# esp32.net
KiCad netlist of a schematic drawn in Altium Designer
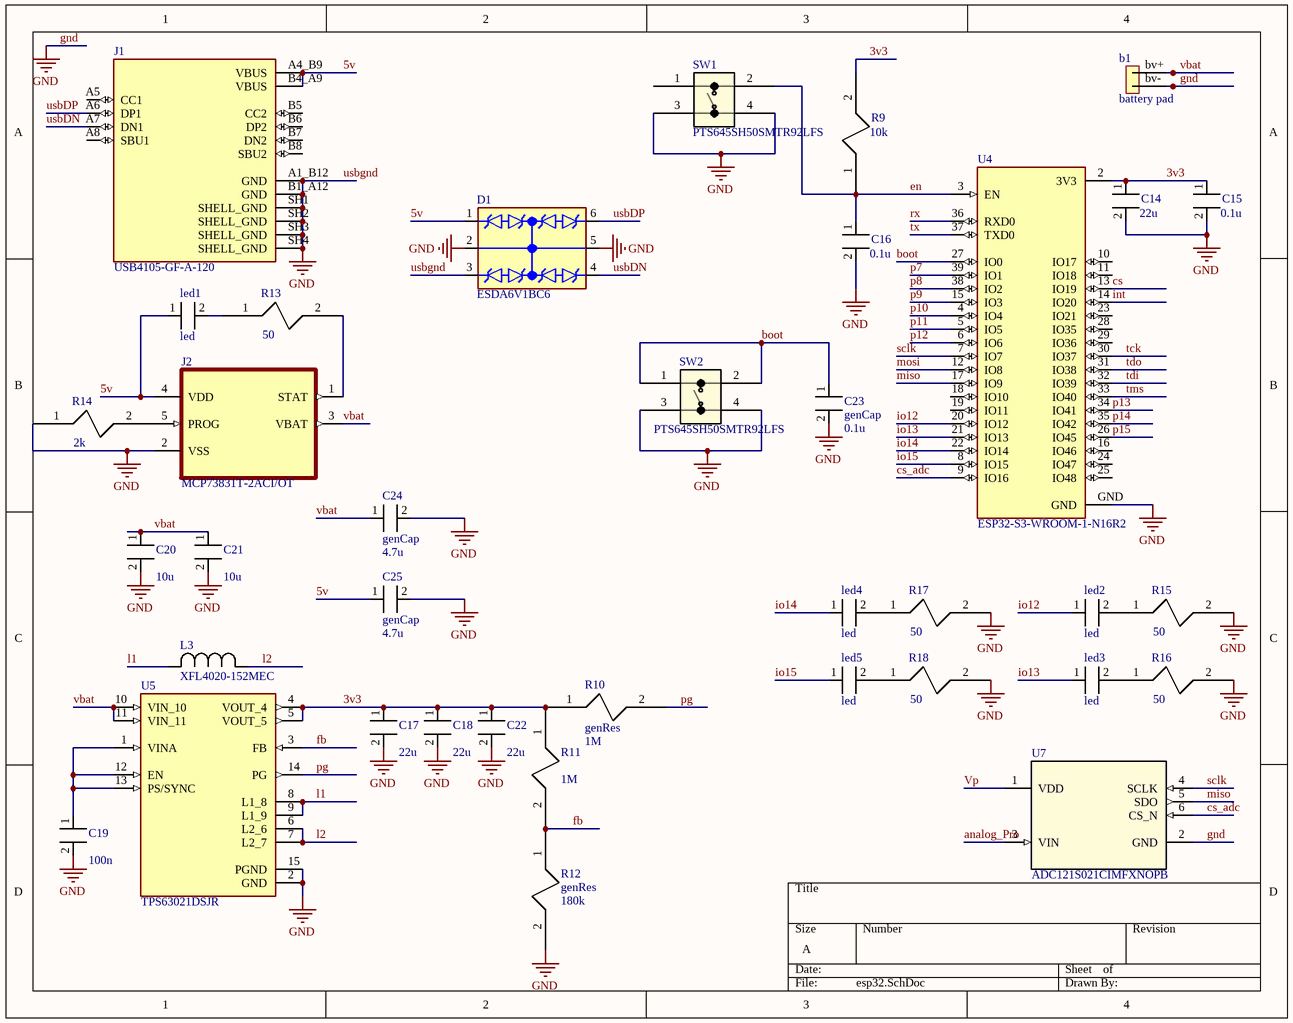
[diagram p0: esp32.SchDoc]

(export (version "E")
  (design (tool "Eeschema 10.0.6"))
  (components
    (comp (ref "b1")
      (value "battery pad")
      (footprint "bat_pads")
      (libsource (lib "sEMG_lib") (part "battery pad"))
    )
    (comp (ref "C14")
      (value "genCap")
      (footprint "GeneralCap")
      (description "C86295")
      (fields (field (name "C") "22u"))
      (libsource (lib "seniorDesign") (part "genCap"))
    )
    (comp (ref "C15")
      (value "genCap")
      (footprint "GeneralCap")
      (description "C14663")
      (fields (field (name "C") "0.1u"))
      (libsource (lib "seniorDesign") (part "genCap"))
    )
    (comp (ref "C16")
      (value "genCap")
      (footprint "GeneralCap")
      (description "C14663")
      (fields (field (name "C") "0.1u"))
      (libsource (lib "seniorDesign") (part "genCap"))
    )
    (comp (ref "C17")
      (value "genCap")
      (footprint "GeneralCap")
      (description "C86295")
      (fields (field (name "C") "22u"))
      (libsource (lib "seniorDesign") (part "genCap"))
    )
    (comp (ref "C18")
      (value "genCap")
      (footprint "GeneralCap")
      (description "C86295")
      (fields (field (name "C") "22u"))
      (libsource (lib "seniorDesign") (part "genCap"))
    )
    (comp (ref "C19")
      (value "genCap")
      (footprint "GeneralCap")
      (description "C14663")
      (fields (field (name "C") "100n"))
      (libsource (lib "seniorDesign") (part "genCap"))
    )
    (comp (ref "C20")
      (value "genCap")
      (footprint "GeneralCap")
      (description "C6119842")
      (fields (field (name "C") "10u"))
      (libsource (lib "seniorDesign") (part "genCap"))
    )
    (comp (ref "C21")
      (value "genCap")
      (footprint "GeneralCap")
      (description "C6119842")
      (fields (field (name "C") "10u"))
      (libsource (lib "seniorDesign") (part "genCap"))
    )
    (comp (ref "C22")
      (value "genCap")
      (footprint "GeneralCap")
      (description "C86295")
      (fields (field (name "C") "22u"))
      (libsource (lib "seniorDesign") (part "genCap"))
    )
    (comp (ref "C23")
      (value "genCap")
      (footprint "GeneralCap")
      (description "C14663")
      (fields (field (name "C") "0.1u"))
      (libsource (lib "seniorDesign") (part "genCap"))
    )
    (comp (ref "C24")
      (value "genCap")
      (footprint "GeneralCap")
      (description "C19666")
      (fields (field (name "C") "4.7u"))
      (libsource (lib "seniorDesign") (part "genCap"))
    )
    (comp (ref "C25")
      (value "genCap")
      (footprint "GeneralCap")
      (description "C19666")
      (fields (field (name "C") "4.7u"))
      (libsource (lib "seniorDesign") (part "genCap"))
    )
    (comp (ref "D1")
      (value "ESDA6V1BC6")
      (footprint "SOT95P280X145-6N")
      (description "C495220")
      (fields (field (name "MF") "STMicroelectronics"))
      (libsource (lib "ESDA6V1BC6") (part "ESDA6V1BC6"))
    )
    (comp (ref "J1")
      (value "USB4105-GF-A-120")
      (footprint "GCT_USB4105-GF-A-120")
      (fields (field (name "MF") "Global Connector Technology") (field (name "MP") "USB4105GFA120"))
      (libsource (lib "USB4105-GF-A-120") (part "USB4105-GF-A-120"))
    )
    (comp (ref "J2")
      (value "MCP73831T-2ACI/OT")
      (footprint "SOT95P280X145-5N")
      (description "C424093")
      (fields (field (name "MF") "Microchip"))
      (libsource (lib "MCP73831T-2ACI_OT") (part "MCP73831T-2ACI/OT"))
    )
    (comp (ref "L3")
      (value "XFL4020-152MEC")
      (footprint "IND_XFL4020_COC")
      (description "C3033018")
      (libsource (lib "XFL4020-152MEC") (part "XFL4020-152MEC"))
    )
    (comp (ref "led1")
      (value "led")
      (footprint "GeneralCap")
      (description "C965799")
      (libsource (lib "seniorDesign") (part "genCap"))
    )
    (comp (ref "led2")
      (value "led")
      (footprint "GeneralCap")
      (description "C965799")
      (libsource (lib "seniorDesign") (part "genCap"))
    )
    (comp (ref "led3")
      (value "led")
      (footprint "GeneralCap")
      (description "C965799")
      (libsource (lib "seniorDesign") (part "genCap"))
    )
    (comp (ref "led4")
      (value "led")
      (footprint "GeneralCap")
      (description "C965799")
      (libsource (lib "seniorDesign") (part "genCap"))
    )
    (comp (ref "led5")
      (value "led")
      (footprint "GeneralCap")
      (description "C965799")
      (libsource (lib "seniorDesign") (part "genCap"))
    )
    (comp (ref "R9")
      (value "genRes")
      (footprint "GeneralCap")
      (description "C98220")
      (fields (field (name "R") "10k"))
      (libsource (lib "seniorDesign") (part "genRes"))
    )
    (comp (ref "R10")
      (value "genRes")
      (footprint "GeneralCap")
      (description "C105578")
      (fields (field (name "R") "1M"))
      (libsource (lib "seniorDesign") (part "genRes"))
    )
    (comp (ref "R11")
      (value "genRes")
      (footprint "GeneralCap")
      (description "C105578")
      (fields (field (name "R") "1M"))
      (libsource (lib "seniorDesign") (part "genRes"))
    )
    (comp (ref "R12")
      (value "genRes")
      (footprint "GeneralCap")
      (description "C123419")
      (fields (field (name "R") "180k"))
      (libsource (lib "seniorDesign") (part "genRes"))
    )
    (comp (ref "R13")
      (value "genRes")
      (footprint "GeneralCap")
      (description "C844932")
      (fields (field (name "R") "50"))
      (libsource (lib "seniorDesign") (part "genRes"))
    )
    (comp (ref "R14")
      (value "genRes")
      (footprint "GeneralCap")
      (description "C22975")
      (fields (field (name "R") "2k"))
      (libsource (lib "seniorDesign") (part "genRes"))
    )
    (comp (ref "R15")
      (value "genRes")
      (footprint "GeneralCap")
      (description "C844932")
      (fields (field (name "R") "50"))
      (libsource (lib "seniorDesign") (part "genRes"))
    )
    (comp (ref "R16")
      (value "genRes")
      (footprint "GeneralCap")
      (description "C844932")
      (fields (field (name "R") "50"))
      (libsource (lib "seniorDesign") (part "genRes"))
    )
    (comp (ref "R17")
      (value "genRes")
      (footprint "GeneralCap")
      (description "C844932")
      (fields (field (name "R") "50"))
      (libsource (lib "seniorDesign") (part "genRes"))
    )
    (comp (ref "R18")
      (value "genRes")
      (footprint "GeneralCap")
      (description "C844932")
      (fields (field (name "R") "50"))
      (libsource (lib "seniorDesign") (part "genRes"))
    )
    (comp (ref "SW1")
      (value "PTS645SH50SMTR92LFS")
      (footprint "PTS645S_SMTR92_CNK")
      (description "C221869")
      (libsource (lib "PTS645SH50SMTR92LFS") (part "PTS645SH50SMTR92LFS"))
    )
    (comp (ref "SW2")
      (value "PTS645SH50SMTR92LFS")
      (footprint "PTS645S_SMTR92_CNK")
      (description "C221869")
      (libsource (lib "PTS645SH50SMTR92LFS") (part "PTS645SH50SMTR92LFS"))
    )
    (comp (ref "U4")
      (value "ESP32-S3-WROOM-1-N16R2")
      (footprint "XCVR_ESP32-S3-WROOM-1-N16R2")
      (description "C2913205")
      (fields (field (name "MF") "Espressif Systems") (field (name "MP") "ESP32S3WROOM1N16R2"))
      (libsource (lib "ESP32-S3-WROOM-1-N16R2") (part "ESP32-S3-WROOM-1-N16R2"))
    )
    (comp (ref "U5")
      (value "TPS63021DSJR")
      (footprint "IC_TPS63021DSJR")
      (libsource (lib "TPS63021DSJR") (part "TPS63021DSJR"))
    )
    (comp (ref "U7")
      (value "ADC121S021CIMFXNOPB")
      (footprint "DBV0006A_N")
      (description "C701596")
      (libsource (lib "ADC121S021CIMFXNOPB") (part "ADC121S021CIMFXNOPB"))
    )
  )
  (nets
    (net (code "1") (name "/3v3") (class "Default")
      (node (ref "C14") (pin "1") (pinfunction "1_1") (pintype "passive"))
      (node (ref "C15") (pin "1") (pinfunction "1_1") (pintype "passive"))
      (node (ref "C17") (pin "1") (pinfunction "1_1") (pintype "passive"))
      (node (ref "C18") (pin "1") (pinfunction "1_1") (pintype "passive"))
      (node (ref "C22") (pin "1") (pinfunction "1_1") (pintype "passive"))
      (node (ref "R10") (pin "1") (pinfunction "1_1") (pintype "passive"))
      (node (ref "R11") (pin "1") (pinfunction "1_1") (pintype "passive"))
      (node (ref "R9") (pin "2") (pinfunction "2_2") (pintype "passive"))
      (node (ref "U4") (pin "2") (pinfunction "3V3_2") (pintype "power_in"))
      (node (ref "U5") (pin "4") (pinfunction "VOUT_4_4") (pintype "output"))
      (node (ref "U5") (pin "5") (pinfunction "VOUT_5_5") (pintype "output"))
    )
    (net (code "2") (name "/5v") (class "Default")
      (node (ref "C25") (pin "1") (pinfunction "1_1") (pintype "passive"))
      (node (ref "D1") (pin "1") (pinfunction "C1_1") (pintype "passive"))
      (node (ref "J1") (pin "A4_B9") (pinfunction "VBUS_A4_B9") (pintype "power_in"))
      (node (ref "J1") (pin "B4_A9") (pinfunction "VBUS_B4_A9") (pintype "power_in"))
      (node (ref "J2") (pin "4") (pinfunction "VDD_4") (pintype "power_in"))
      (node (ref "led1") (pin "1") (pinfunction "1_1") (pintype "passive"))
    )
    (net (code "3") (name "/Vp") (class "Default")
      (node (ref "U7") (pin "1") (pinfunction "VDD_1") (pintype "power_in"))
    )
    (net (code "4") (name "/analog_Pro") (class "Default")
      (node (ref "U7") (pin "3") (pinfunction "VIN_3") (pintype "input"))
    )
    (net (code "5") (name "/boot") (class "Default")
      (node (ref "C23") (pin "1") (pinfunction "1_1") (pintype "passive"))
      (node (ref "SW2") (pin "1") (pinfunction "1_1") (pintype "passive"))
      (node (ref "SW2") (pin "2") (pinfunction "2_2") (pintype "passive"))
      (node (ref "U4") (pin "27") (pinfunction "IO0_27") (pintype "bidirectional"))
    )
    (net (code "6") (name "/cs") (class "Default")
      (node (ref "U4") (pin "13") (pinfunction "IO19_13") (pintype "bidirectional"))
    )
    (net (code "7") (name "/cs_adc") (class "Default")
      (node (ref "U4") (pin "9") (pinfunction "IO16_9") (pintype "bidirectional"))
      (node (ref "U7") (pin "6") (pinfunction "CS_N_6") (pintype "input"))
    )
    (net (code "8") (name "/en") (class "Default")
      (node (ref "C16") (pin "1") (pinfunction "1_1") (pintype "passive"))
      (node (ref "R9") (pin "1") (pinfunction "1_1") (pintype "passive"))
      (node (ref "SW1") (pin "2") (pinfunction "2_2") (pintype "passive"))
      (node (ref "U4") (pin "3") (pinfunction "EN_3") (pintype "input"))
    )
    (net (code "9") (name "/fb") (class "Default")
      (node (ref "R11") (pin "2") (pinfunction "2_2") (pintype "passive"))
      (node (ref "R12") (pin "1") (pinfunction "1_1") (pintype "passive"))
      (node (ref "U5") (pin "3") (pinfunction "FB_3") (pintype "input"))
    )
    (net (code "10") (name "/int") (class "Default")
      (node (ref "U4") (pin "14") (pinfunction "IO20_14") (pintype "bidirectional"))
    )
    (net (code "11") (name "/io12") (class "Default")
      (node (ref "U4") (pin "20") (pinfunction "IO12_20") (pintype "bidirectional"))
      (node (ref "led2") (pin "1") (pinfunction "1_1") (pintype "passive"))
    )
    (net (code "12") (name "/io13") (class "Default")
      (node (ref "U4") (pin "21") (pinfunction "IO13_21") (pintype "bidirectional"))
      (node (ref "led3") (pin "1") (pinfunction "1_1") (pintype "passive"))
    )
    (net (code "13") (name "/io14") (class "Default")
      (node (ref "U4") (pin "22") (pinfunction "IO14_22") (pintype "bidirectional"))
      (node (ref "led4") (pin "1") (pinfunction "1_1") (pintype "passive"))
    )
    (net (code "14") (name "/io15") (class "Default")
      (node (ref "U4") (pin "8") (pinfunction "IO15_8") (pintype "bidirectional"))
      (node (ref "led5") (pin "1") (pinfunction "1_1") (pintype "passive"))
    )
    (net (code "15") (name "/l1") (class "Default")
      (node (ref "L3") (pin "2") (pinfunction "2_2") (pintype "passive"))
      (node (ref "U5") (pin "8") (pinfunction "L1_8_8") (pintype "passive"))
      (node (ref "U5") (pin "9") (pinfunction "L1_9_9") (pintype "passive"))
    )
    (net (code "16") (name "/l2") (class "Default")
      (node (ref "L3") (pin "1") (pinfunction "1_1") (pintype "passive"))
      (node (ref "U5") (pin "6") (pinfunction "L2_6_6") (pintype "passive"))
      (node (ref "U5") (pin "7") (pinfunction "L2_7_7") (pintype "passive"))
    )
    (net (code "17") (name "/miso") (class "Default")
      (node (ref "U4") (pin "17") (pinfunction "IO9_17") (pintype "bidirectional"))
      (node (ref "U7") (pin "5") (pinfunction "SDO_5") (pintype "output"))
    )
    (net (code "18") (name "/mosi") (class "Default")
      (node (ref "U4") (pin "12") (pinfunction "IO8_12") (pintype "bidirectional"))
    )
    (net (code "19") (name "/p7") (class "Default")
      (node (ref "U4") (pin "39") (pinfunction "IO1_39") (pintype "bidirectional"))
    )
    (net (code "20") (name "/p8") (class "Default")
      (node (ref "U4") (pin "38") (pinfunction "IO2_38") (pintype "bidirectional"))
    )
    (net (code "21") (name "/p9") (class "Default")
      (node (ref "U4") (pin "15") (pinfunction "IO3_15") (pintype "bidirectional"))
    )
    (net (code "22") (name "/p10") (class "Default")
      (node (ref "U4") (pin "4") (pinfunction "IO4_4") (pintype "bidirectional"))
    )
    (net (code "23") (name "/p11") (class "Default")
      (node (ref "U4") (pin "5") (pinfunction "IO5_5") (pintype "bidirectional"))
    )
    (net (code "24") (name "/p12") (class "Default")
      (node (ref "U4") (pin "6") (pinfunction "IO6_6") (pintype "bidirectional"))
    )
    (net (code "25") (name "/p13") (class "Default")
      (node (ref "U4") (pin "34") (pinfunction "IO41_34") (pintype "bidirectional"))
    )
    (net (code "26") (name "/p14") (class "Default")
      (node (ref "U4") (pin "35") (pinfunction "IO42_35") (pintype "bidirectional"))
    )
    (net (code "27") (name "/p15") (class "Default")
      (node (ref "U4") (pin "26") (pinfunction "IO45_26") (pintype "bidirectional"))
    )
    (net (code "28") (name "/pg") (class "Default")
      (node (ref "R10") (pin "2") (pinfunction "2_2") (pintype "passive"))
      (node (ref "U5") (pin "14") (pinfunction "PG_14") (pintype "output"))
    )
    (net (code "29") (name "/rx") (class "Default")
      (node (ref "U4") (pin "36") (pinfunction "RXD0_36") (pintype "bidirectional"))
    )
    (net (code "30") (name "/sclk") (class "Default")
      (node (ref "U4") (pin "7") (pinfunction "IO7_7") (pintype "bidirectional"))
      (node (ref "U7") (pin "4") (pinfunction "SCLK_4") (pintype "input"))
    )
    (net (code "31") (name "/tck") (class "Default")
      (node (ref "U4") (pin "30") (pinfunction "IO37_30") (pintype "bidirectional"))
    )
    (net (code "32") (name "/tdi") (class "Default")
      (node (ref "U4") (pin "32") (pinfunction "IO39_32") (pintype "bidirectional"))
    )
    (net (code "33") (name "/tdo") (class "Default")
      (node (ref "U4") (pin "31") (pinfunction "IO38_31") (pintype "bidirectional"))
    )
    (net (code "34") (name "/tms") (class "Default")
      (node (ref "U4") (pin "33") (pinfunction "IO40_33") (pintype "bidirectional"))
    )
    (net (code "35") (name "/tx") (class "Default")
      (node (ref "U4") (pin "37") (pinfunction "TXD0_37") (pintype "bidirectional"))
    )
    (net (code "36") (name "/usbDN") (class "Default")
      (node (ref "D1") (pin "4") (pinfunction "C3_4") (pintype "passive"))
      (node (ref "J1") (pin "A7") (pinfunction "DN1_A7") (pintype "bidirectional"))
    )
    (net (code "37") (name "/usbDP") (class "Default")
      (node (ref "D1") (pin "6") (pinfunction "C4_6") (pintype "passive"))
      (node (ref "J1") (pin "A6") (pinfunction "DP1_A6") (pintype "bidirectional"))
    )
    (net (code "38") (name "/vbat") (class "Default")
      (node (ref "C20") (pin "1") (pinfunction "1_1") (pintype "passive"))
      (node (ref "C21") (pin "1") (pinfunction "1_1") (pintype "passive"))
      (node (ref "C24") (pin "1") (pinfunction "1_1") (pintype "passive"))
      (node (ref "J2") (pin "3") (pinfunction "VBAT_3") (pintype "output"))
      (node (ref "U5") (pin "10") (pinfunction "VIN_10_10") (pintype "input"))
      (node (ref "U5") (pin "11") (pinfunction "VIN_11_11") (pintype "input"))
      (node (ref "b1") (pin "bv+") (pinfunction "bv+_bv+") (pintype "passive"))
    )
    (net (code "39") (name "GND") (class "Default")
      (node (ref "C14") (pin "2") (pinfunction "2_2") (pintype "passive"))
      (node (ref "C15") (pin "2") (pinfunction "2_2") (pintype "passive"))
      (node (ref "C16") (pin "2") (pinfunction "2_2") (pintype "passive"))
      (node (ref "C17") (pin "2") (pinfunction "2_2") (pintype "passive"))
      (node (ref "C18") (pin "2") (pinfunction "2_2") (pintype "passive"))
      (node (ref "C19") (pin "2") (pinfunction "2_2") (pintype "passive"))
      (node (ref "C20") (pin "2") (pinfunction "2_2") (pintype "passive"))
      (node (ref "C21") (pin "2") (pinfunction "2_2") (pintype "passive"))
      (node (ref "C22") (pin "2") (pinfunction "2_2") (pintype "passive"))
      (node (ref "C23") (pin "2") (pinfunction "2_2") (pintype "passive"))
      (node (ref "C24") (pin "2") (pinfunction "2_2") (pintype "passive"))
      (node (ref "C25") (pin "2") (pinfunction "2_2") (pintype "passive"))
      (node (ref "D1") (pin "2") (pinfunction "CC1_2") (pintype "passive"))
      (node (ref "D1") (pin "3") (pinfunction "C2_3") (pintype "passive"))
      (node (ref "D1") (pin "5") (pinfunction "CC2_5") (pintype "passive"))
      (node (ref "J1") (pin "A1_B12") (pinfunction "GND_A1_B12") (pintype "power_in"))
      (node (ref "J1") (pin "B1_A12") (pinfunction "GND_B1_A12") (pintype "power_in"))
      (node (ref "J1") (pin "SH1") (pinfunction "SHELL_GND_SH1") (pintype "power_in"))
      (node (ref "J1") (pin "SH2") (pinfunction "SHELL_GND_SH2") (pintype "power_in"))
      (node (ref "J1") (pin "SH3") (pinfunction "SHELL_GND_SH3") (pintype "power_in"))
      (node (ref "J1") (pin "SH4") (pinfunction "SHELL_GND_SH4") (pintype "power_in"))
      (node (ref "J2") (pin "2") (pinfunction "VSS_2") (pintype "power_in"))
      (node (ref "R12") (pin "2") (pinfunction "2_2") (pintype "passive"))
      (node (ref "R14") (pin "1") (pinfunction "1_1") (pintype "passive"))
      (node (ref "R15") (pin "2") (pinfunction "2_2") (pintype "passive"))
      (node (ref "R16") (pin "2") (pinfunction "2_2") (pintype "passive"))
      (node (ref "R17") (pin "2") (pinfunction "2_2") (pintype "passive"))
      (node (ref "R18") (pin "2") (pinfunction "2_2") (pintype "passive"))
      (node (ref "SW1") (pin "3") (pinfunction "3_3") (pintype "passive"))
      (node (ref "SW1") (pin "4") (pinfunction "4_4") (pintype "passive"))
      (node (ref "SW2") (pin "3") (pinfunction "3_3") (pintype "passive"))
      (node (ref "SW2") (pin "4") (pinfunction "4_4") (pintype "passive"))
      (node (ref "U4") (pin "GND") (pinfunction "GND_GND") (pintype "power_in"))
      (node (ref "U5") (pin "15") (pinfunction "PGND_15") (pintype "power_in"))
      (node (ref "U5") (pin "2") (pinfunction "GND_2") (pintype "power_in"))
      (node (ref "U7") (pin "2") (pinfunction "GND_2") (pintype "power_in"))
      (node (ref "b1") (pin "bv-") (pinfunction "bv-_bv-") (pintype "passive"))
    )
    (net (code "40") (name "Net-(J2-PROG)") (class "Default")
      (node (ref "J2") (pin "5") (pinfunction "PROG_5") (pintype "input"))
      (node (ref "R14") (pin "2") (pinfunction "2_2") (pintype "passive"))
    )
    (net (code "41") (name "Net-(J2-STAT)") (class "Default")
      (node (ref "J2") (pin "1") (pinfunction "STAT_1") (pintype "output"))
      (node (ref "R13") (pin "2") (pinfunction "2_2") (pintype "passive"))
    )
    (net (code "42") (name "Net-(R13-Pad1)") (class "Default")
      (node (ref "R13") (pin "1") (pinfunction "1_1") (pintype "passive"))
      (node (ref "led1") (pin "2") (pinfunction "2_2") (pintype "passive"))
    )
    (net (code "43") (name "Net-(R15-Pad1)") (class "Default")
      (node (ref "R15") (pin "1") (pinfunction "1_1") (pintype "passive"))
      (node (ref "led2") (pin "2") (pinfunction "2_2") (pintype "passive"))
    )
    (net (code "44") (name "Net-(R16-Pad1)") (class "Default")
      (node (ref "R16") (pin "1") (pinfunction "1_1") (pintype "passive"))
      (node (ref "led3") (pin "2") (pinfunction "2_2") (pintype "passive"))
    )
    (net (code "45") (name "Net-(R17-Pad1)") (class "Default")
      (node (ref "R17") (pin "1") (pinfunction "1_1") (pintype "passive"))
      (node (ref "led4") (pin "2") (pinfunction "2_2") (pintype "passive"))
    )
    (net (code "46") (name "Net-(R18-Pad1)") (class "Default")
      (node (ref "R18") (pin "1") (pinfunction "1_1") (pintype "passive"))
      (node (ref "led5") (pin "2") (pinfunction "2_2") (pintype "passive"))
    )
    (net (code "47") (name "Net-(U5-EN)") (class "Default")
      (node (ref "C19") (pin "1") (pinfunction "1_1") (pintype "passive"))
      (node (ref "U5") (pin "1") (pinfunction "VINA_1") (pintype "input"))
      (node (ref "U5") (pin "12") (pinfunction "EN_12") (pintype "input"))
      (node (ref "U5") (pin "13") (pinfunction "PS/SYNC_13") (pintype "input"))
    )
    (net (code "48") (name "unconnected-(J1-CC1-PadA5)") (class "Default")
      (node (ref "J1") (pin "A5") (pinfunction "CC1_A5") (pintype "bidirectional"))
    )
    (net (code "49") (name "unconnected-(J1-CC2-PadB5)") (class "Default")
      (node (ref "J1") (pin "B5") (pinfunction "CC2_B5") (pintype "bidirectional"))
    )
    (net (code "50") (name "unconnected-(J1-DN2-PadB7)") (class "Default")
      (node (ref "J1") (pin "B7") (pinfunction "DN2_B7") (pintype "bidirectional"))
    )
    (net (code "51") (name "unconnected-(J1-DP2-PadB6)") (class "Default")
      (node (ref "J1") (pin "B6") (pinfunction "DP2_B6") (pintype "bidirectional"))
    )
    (net (code "52") (name "unconnected-(J1-SBU1-PadA8)") (class "Default")
      (node (ref "J1") (pin "A8") (pinfunction "SBU1_A8") (pintype "bidirectional"))
    )
    (net (code "53") (name "unconnected-(J1-SBU2-PadB8)") (class "Default")
      (node (ref "J1") (pin "B8") (pinfunction "SBU2_B8") (pintype "bidirectional"))
    )
    (net (code "54") (name "unconnected-(SW1-Pad1)") (class "Default")
      (node (ref "SW1") (pin "1") (pinfunction "1_1") (pintype "passive"))
    )
    (net (code "55") (name "unconnected-(U4-IO10-Pad18)") (class "Default")
      (node (ref "U4") (pin "18") (pinfunction "IO10_18") (pintype "bidirectional"))
    )
    (net (code "56") (name "unconnected-(U4-IO11-Pad19)") (class "Default")
      (node (ref "U4") (pin "19") (pinfunction "IO11_19") (pintype "bidirectional"))
    )
    (net (code "57") (name "unconnected-(U4-IO17-Pad10)") (class "Default")
      (node (ref "U4") (pin "10") (pinfunction "IO17_10") (pintype "bidirectional"))
    )
    (net (code "58") (name "unconnected-(U4-IO18-Pad11)") (class "Default")
      (node (ref "U4") (pin "11") (pinfunction "IO18_11") (pintype "bidirectional"))
    )
    (net (code "59") (name "unconnected-(U4-IO21-Pad23)") (class "Default")
      (node (ref "U4") (pin "23") (pinfunction "IO21_23") (pintype "bidirectional"))
    )
    (net (code "60") (name "unconnected-(U4-IO35-Pad28)") (class "Default")
      (node (ref "U4") (pin "28") (pinfunction "IO35_28") (pintype "bidirectional"))
    )
    (net (code "61") (name "unconnected-(U4-IO36-Pad29)") (class "Default")
      (node (ref "U4") (pin "29") (pinfunction "IO36_29") (pintype "bidirectional"))
    )
    (net (code "62") (name "unconnected-(U4-IO46-Pad16)") (class "Default")
      (node (ref "U4") (pin "16") (pinfunction "IO46_16") (pintype "bidirectional"))
    )
    (net (code "63") (name "unconnected-(U4-IO47-Pad24)") (class "Default")
      (node (ref "U4") (pin "24") (pinfunction "IO47_24") (pintype "bidirectional"))
    )
    (net (code "64") (name "unconnected-(U4-IO48-Pad25)") (class "Default")
      (node (ref "U4") (pin "25") (pinfunction "IO48_25") (pintype "bidirectional"))
    )
  )
)
